# Test.net
KiCad netlist of a schematic drawn in EAGLE
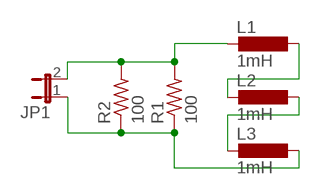
[diagram p0: schematic, sheet 1]

(export (version "E")
  (design (tool "Eeschema 10.0.6"))
  (components
    (comp (ref "JP1")
      (value "JP1E")
      (footprint "eagle-import:JP1")
      (libsource (lib "eagle-import") (part "JP1E"))
    )
    (comp (ref "L1")
      (value "1mH")
      (footprint "eagle-import:DO3316P")
      (libsource (lib "eagle-import") (part "DO3316P"))
    )
    (comp (ref "L2")
      (value "1mH")
      (footprint "eagle-import:DO3316P")
      (libsource (lib "eagle-import") (part "DO3316P"))
    )
    (comp (ref "L3")
      (value "1mH")
      (footprint "eagle-import:DO3316P")
      (libsource (lib "eagle-import") (part "DO3316P"))
    )
    (comp (ref "R1")
      (value "100")
      (footprint "eagle-import:R0603")
      (libsource (lib "eagle-import") (part "R-US_R0603"))
    )
    (comp (ref "R2")
      (value "100")
      (footprint "eagle-import:R0603")
      (libsource (lib "eagle-import") (part "R-US_R0603"))
    )
  )
  (nets
    (net (code "1") (name "Net-(JP1-Pad1)") (class "Default")
      (node (ref "JP1") (pin "1") (pinfunction "1_1") (pintype "passive"))
      (node (ref "L3") (pin "2") (pinfunction "2_2") (pintype "passive"))
      (node (ref "R1") (pin "1") (pinfunction "1_1") (pintype "passive"))
      (node (ref "R2") (pin "1") (pinfunction "1_1") (pintype "passive"))
    )
    (net (code "2") (name "Net-(JP1-Pad2)") (class "Default")
      (node (ref "JP1") (pin "2") (pinfunction "2_2") (pintype "passive"))
      (node (ref "L1") (pin "1") (pinfunction "1_1") (pintype "passive"))
      (node (ref "R1") (pin "2") (pinfunction "2_2") (pintype "passive"))
      (node (ref "R2") (pin "2") (pinfunction "2_2") (pintype "passive"))
    )
    (net (code "3") (name "Net-(L1-Pad2)") (class "Default")
      (node (ref "L1") (pin "2") (pinfunction "2_2") (pintype "passive"))
      (node (ref "L2") (pin "1") (pinfunction "1_1") (pintype "passive"))
    )
    (net (code "4") (name "Net-(L2-Pad2)") (class "Default")
      (node (ref "L2") (pin "2") (pinfunction "2_2") (pintype "passive"))
      (node (ref "L3") (pin "1") (pinfunction "1_1") (pintype "passive"))
    )
  )
)
